# GSM.net
KiCad netlist of a schematic drawn in Altium Designer
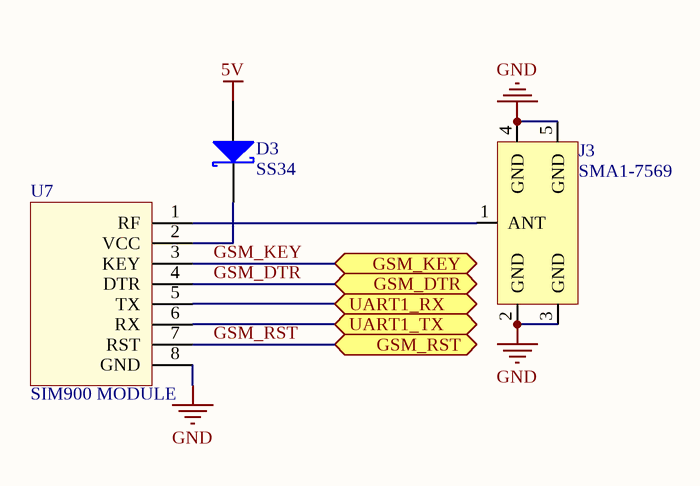
[diagram p0: GSM.SchDoc]

(export (version "E")
  (design (tool "Eeschema 10.0.6"))
  (components
    (comp (ref "D3")
      (value "SS34")
      (footprint "DO-214AC (SMA)")
      (description "DIODE SCHOTTKY 40V 3A SMA")
      (fields
        (field (name "DIGI-KEY PART NUMBER") "B340A-E3/61TGITR-ND")
        (field (name "MANUFACTURER PART NUMBER") "B340A-E3/61T")
        (field (name "PUBLISHER") "Altium Limited")
      )
      (libsource (lib "RobotClub") (part "D Schottky"))
    )
    (comp (ref "J3")
      (value "SMA1-7569")
      (footprint "ANTENA STAND")
      (description "SMA-R/A-F")
      (fields (field (name "DIGI-KEY PART NUMBER") "NA"))
      (libsource (lib "RobotClub") (part "SMA-R/A-F"))
    )
    (comp (ref "U7")
      (value "SIM900 MODULE")
      (footprint "SIM900 DEMETER")
      (libsource (lib "RobotClub") (part "SIM900 MODULE"))
    )
  )
  (nets
    (net (code "1") (name "/GSM_DTR") (class "Default")
      (node (ref "U7") (pin "4") (pinfunction "DTR_4") (pintype "passive"))
    )
    (net (code "2") (name "/GSM_KEY") (class "Default")
      (node (ref "U7") (pin "3") (pinfunction "KEY_3") (pintype "passive"))
    )
    (net (code "3") (name "/GSM_RST") (class "Default")
      (node (ref "U7") (pin "7") (pinfunction "RST_7") (pintype "passive"))
    )
    (net (code "4") (name "/UART1_RX") (class "Default")
      (node (ref "U7") (pin "5") (pinfunction "TX_5") (pintype "passive"))
    )
    (net (code "5") (name "/UART1_TX") (class "Default")
      (node (ref "U7") (pin "6") (pinfunction "RX_6") (pintype "passive"))
    )
    (net (code "6") (name "5V") (class "Default")
      (node (ref "D3") (pin "1") (pinfunction "A_1") (pintype "passive"))
    )
    (net (code "7") (name "GND") (class "Default")
      (node (ref "J3") (pin "2") (pinfunction "GND_2") (pintype "passive"))
      (node (ref "J3") (pin "3") (pinfunction "GND_3") (pintype "passive"))
      (node (ref "J3") (pin "4") (pinfunction "GND_4") (pintype "passive"))
      (node (ref "J3") (pin "5") (pinfunction "GND_5") (pintype "passive"))
      (node (ref "U7") (pin "8") (pinfunction "GND_8") (pintype "passive"))
    )
    (net (code "8") (name "Net-(D3-K)") (class "Default")
      (node (ref "D3") (pin "2") (pinfunction "K_2") (pintype "passive"))
      (node (ref "U7") (pin "2") (pinfunction "VCC_2") (pintype "passive"))
    )
    (net (code "9") (name "Net-(J3-ANT)") (class "Default")
      (node (ref "J3") (pin "1") (pinfunction "ANT_1") (pintype "passive"))
      (node (ref "U7") (pin "1") (pinfunction "RF_1") (pintype "passive"))
    )
  )
)
